# W707H.net
KiCad netlist of a schematic drawn in EAGLE
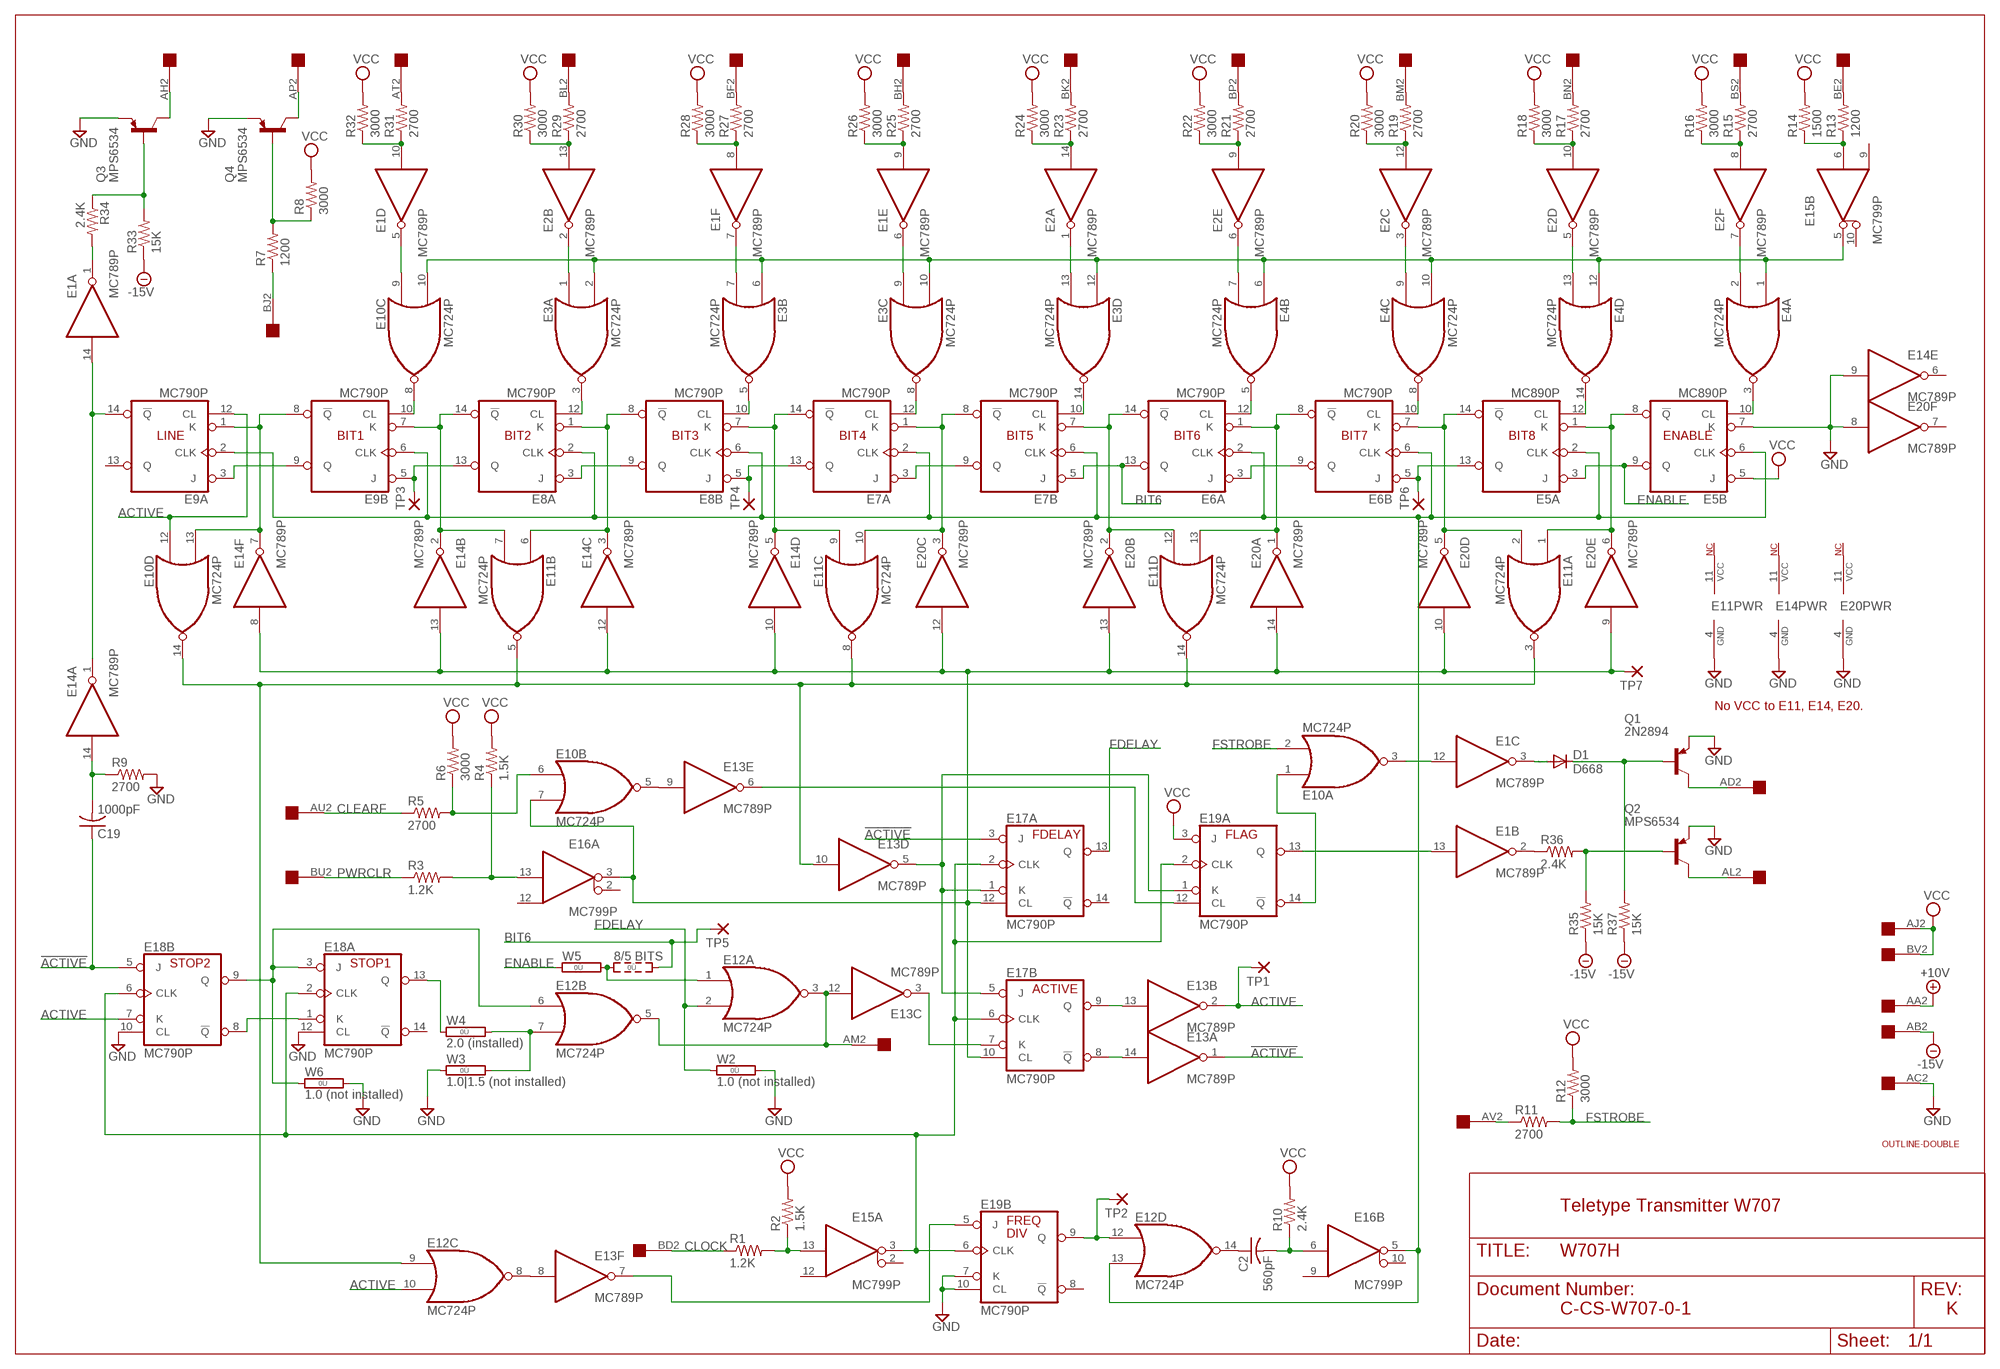
[diagram p0: schematic, sheet 1]

(export (version "E")
  (design (tool "Eeschema 10.0.6"))
  (components
    (comp (ref "C2")
      (value "560pF")
      (footprint "eagle-import:C050-025X075")
      (libsource (lib "eagle-import") (part "C-US050-025X075"))
    )
    (comp (ref "C19")
      (value "1000pF")
      (footprint "eagle-import:C050-025X075")
      (libsource (lib "eagle-import") (part "C-US050-025X075"))
    )
    (comp (ref "D1")
      (value "D668")
      (footprint "eagle-import:DO35-10")
      (libsource (lib "eagle-import") (part "1N4148DO35-10"))
    )
    (comp (ref "E1")
      (value "MC789P")
      (footprint "eagle-import:DIL14")
      (libsource (lib "eagle-import") (part "MC889P"))
    )
    (comp (ref "E2")
      (value "MC789P")
      (footprint "eagle-import:DIL14")
      (libsource (lib "eagle-import") (part "MC889P"))
    )
    (comp (ref "E3")
      (value "MC724P")
      (footprint "eagle-import:DIL14")
      (libsource (lib "eagle-import") (part "MC824P"))
    )
    (comp (ref "E4")
      (value "MC724P")
      (footprint "eagle-import:DIL14")
      (libsource (lib "eagle-import") (part "MC824P"))
    )
    (comp (ref "E5")
      (value "MC890P")
      (footprint "eagle-import:DIL14")
      (libsource (lib "eagle-import") (part "MC890P"))
    )
    (comp (ref "E6")
      (value "MC790P")
      (footprint "eagle-import:DIL14")
      (libsource (lib "eagle-import") (part "MC890P"))
    )
    (comp (ref "E7")
      (value "MC790P")
      (footprint "eagle-import:DIL14")
      (libsource (lib "eagle-import") (part "MC890P"))
    )
    (comp (ref "E8")
      (value "MC790P")
      (footprint "eagle-import:DIL14")
      (libsource (lib "eagle-import") (part "MC890P"))
    )
    (comp (ref "E9")
      (value "MC790P")
      (footprint "eagle-import:DIL14")
      (libsource (lib "eagle-import") (part "MC890P"))
    )
    (comp (ref "E10")
      (value "MC724P")
      (footprint "eagle-import:DIL14")
      (libsource (lib "eagle-import") (part "MC824P"))
    )
    (comp (ref "E11")
      (value "MC724P")
      (footprint "eagle-import:DIL14")
      (libsource (lib "eagle-import") (part "MC824P"))
    )
    (comp (ref "E12")
      (value "MC724P")
      (footprint "eagle-import:DIL14")
      (libsource (lib "eagle-import") (part "MC824P"))
    )
    (comp (ref "E13")
      (value "MC789P")
      (footprint "eagle-import:DIL14")
      (libsource (lib "eagle-import") (part "MC889P"))
    )
    (comp (ref "E14")
      (value "MC789P")
      (footprint "eagle-import:DIL14")
      (libsource (lib "eagle-import") (part "MC889P"))
    )
    (comp (ref "E15")
      (value "MC799P")
      (footprint "eagle-import:DIL14")
      (libsource (lib "eagle-import") (part "MC899P"))
    )
    (comp (ref "E16")
      (value "MC799P")
      (footprint "eagle-import:DIL14")
      (libsource (lib "eagle-import") (part "MC899P"))
    )
    (comp (ref "E17")
      (value "MC790P")
      (footprint "eagle-import:DIL14")
      (libsource (lib "eagle-import") (part "MC890P"))
    )
    (comp (ref "E18")
      (value "MC790P")
      (footprint "eagle-import:DIL14")
      (libsource (lib "eagle-import") (part "MC890P"))
    )
    (comp (ref "E19")
      (value "MC790P")
      (footprint "eagle-import:DIL14")
      (libsource (lib "eagle-import") (part "MC890P"))
    )
    (comp (ref "E20")
      (value "MC789P")
      (footprint "eagle-import:DIL14")
      (libsource (lib "eagle-import") (part "MC889P"))
    )
    (comp (ref "Q1")
      (value "2N2894")
      (footprint "eagle-import:TO39")
      (libsource (lib "eagle-import") (part "2N2904"))
    )
    (comp (ref "Q2")
      (value "MPS6534")
      (footprint "eagle-import:TO39")
      (libsource (lib "eagle-import") (part "2N2904"))
    )
    (comp (ref "Q3")
      (value "MPS6534")
      (footprint "eagle-import:TO39")
      (libsource (lib "eagle-import") (part "2N2904"))
    )
    (comp (ref "Q4")
      (value "MPS6534")
      (footprint "eagle-import:TO39")
      (libsource (lib "eagle-import") (part "2N2904"))
    )
    (comp (ref "R1")
      (value "1.2K")
      (footprint "eagle-import:0207_10")
      (libsource (lib "eagle-import") (part "R-US_0207/10"))
    )
    (comp (ref "R2")
      (value "1.5K")
      (footprint "eagle-import:0207_10")
      (libsource (lib "eagle-import") (part "R-US_0207/10"))
    )
    (comp (ref "R3")
      (value "1.2K")
      (footprint "eagle-import:0207_10")
      (libsource (lib "eagle-import") (part "R-US_0207/10"))
    )
    (comp (ref "R4")
      (value "1.5K")
      (footprint "eagle-import:0207_10")
      (libsource (lib "eagle-import") (part "R-US_0207/10"))
    )
    (comp (ref "R5")
      (value "2700")
      (footprint "eagle-import:0207_10")
      (libsource (lib "eagle-import") (part "R-US_0207/10"))
    )
    (comp (ref "R6")
      (value "3000")
      (footprint "eagle-import:0207_10")
      (libsource (lib "eagle-import") (part "R-US_0207/10"))
    )
    (comp (ref "R7")
      (value "1200")
      (footprint "eagle-import:0207_10")
      (libsource (lib "eagle-import") (part "R-US_0207/10"))
    )
    (comp (ref "R8")
      (value "3000")
      (footprint "eagle-import:0207_10")
      (libsource (lib "eagle-import") (part "R-US_0207/10"))
    )
    (comp (ref "R9")
      (value "2700")
      (footprint "eagle-import:0207_10")
      (libsource (lib "eagle-import") (part "R-US_0207/10"))
    )
    (comp (ref "R10")
      (value "2.4K")
      (footprint "eagle-import:0207_10")
      (libsource (lib "eagle-import") (part "R-US_0207/10"))
    )
    (comp (ref "R11")
      (value "2700")
      (footprint "eagle-import:0207_10")
      (libsource (lib "eagle-import") (part "R-US_0207/10"))
    )
    (comp (ref "R12")
      (value "3000")
      (footprint "eagle-import:0207_10")
      (libsource (lib "eagle-import") (part "R-US_0207/10"))
    )
    (comp (ref "R13")
      (value "1200")
      (footprint "eagle-import:0207_10")
      (libsource (lib "eagle-import") (part "R-US_0207/10"))
    )
    (comp (ref "R14")
      (value "1500")
      (footprint "eagle-import:0207_10")
      (libsource (lib "eagle-import") (part "R-US_0207/10"))
    )
    (comp (ref "R15")
      (value "2700")
      (footprint "eagle-import:0207_10")
      (libsource (lib "eagle-import") (part "R-US_0207/10"))
    )
    (comp (ref "R16")
      (value "3000")
      (footprint "eagle-import:0207_10")
      (libsource (lib "eagle-import") (part "R-US_0207/10"))
    )
    (comp (ref "R17")
      (value "2700")
      (footprint "eagle-import:0207_10")
      (libsource (lib "eagle-import") (part "R-US_0207/10"))
    )
    (comp (ref "R18")
      (value "3000")
      (footprint "eagle-import:0207_10")
      (libsource (lib "eagle-import") (part "R-US_0207/10"))
    )
    (comp (ref "R19")
      (value "2700")
      (footprint "eagle-import:0207_10")
      (libsource (lib "eagle-import") (part "R-US_0207/10"))
    )
    (comp (ref "R20")
      (value "3000")
      (footprint "eagle-import:0207_10")
      (libsource (lib "eagle-import") (part "R-US_0207/10"))
    )
    (comp (ref "R21")
      (value "2700")
      (footprint "eagle-import:0207_10")
      (libsource (lib "eagle-import") (part "R-US_0207/10"))
    )
    (comp (ref "R22")
      (value "3000")
      (footprint "eagle-import:0207_10")
      (libsource (lib "eagle-import") (part "R-US_0207/10"))
    )
    (comp (ref "R23")
      (value "2700")
      (footprint "eagle-import:0207_10")
      (libsource (lib "eagle-import") (part "R-US_0207/10"))
    )
    (comp (ref "R24")
      (value "3000")
      (footprint "eagle-import:0207_10")
      (libsource (lib "eagle-import") (part "R-US_0207/10"))
    )
    (comp (ref "R25")
      (value "2700")
      (footprint "eagle-import:0207_10")
      (libsource (lib "eagle-import") (part "R-US_0207/10"))
    )
    (comp (ref "R26")
      (value "3000")
      (footprint "eagle-import:0207_10")
      (libsource (lib "eagle-import") (part "R-US_0207/10"))
    )
    (comp (ref "R27")
      (value "2700")
      (footprint "eagle-import:0207_10")
      (libsource (lib "eagle-import") (part "R-US_0207/10"))
    )
    (comp (ref "R28")
      (value "3000")
      (footprint "eagle-import:0207_10")
      (libsource (lib "eagle-import") (part "R-US_0207/10"))
    )
    (comp (ref "R29")
      (value "2700")
      (footprint "eagle-import:0207_10")
      (libsource (lib "eagle-import") (part "R-US_0207/10"))
    )
    (comp (ref "R30")
      (value "3000")
      (footprint "eagle-import:0207_10")
      (libsource (lib "eagle-import") (part "R-US_0207/10"))
    )
    (comp (ref "R31")
      (value "2700")
      (footprint "eagle-import:0207_10")
      (libsource (lib "eagle-import") (part "R-US_0207/10"))
    )
    (comp (ref "R32")
      (value "3000")
      (footprint "eagle-import:0207_10")
      (libsource (lib "eagle-import") (part "R-US_0207/10"))
    )
    (comp (ref "R33")
      (value "15K")
      (footprint "eagle-import:0207_10")
      (libsource (lib "eagle-import") (part "R-US_0207/10"))
    )
    (comp (ref "R34")
      (value "2.4K")
      (footprint "eagle-import:0207_10")
      (libsource (lib "eagle-import") (part "R-US_0207/10"))
    )
    (comp (ref "R35")
      (value "15K")
      (footprint "eagle-import:0207_10")
      (libsource (lib "eagle-import") (part "R-US_0207/10"))
    )
    (comp (ref "R36")
      (value "2.4K")
      (footprint "eagle-import:0207_10")
      (libsource (lib "eagle-import") (part "R-US_0207/10"))
    )
    (comp (ref "R37")
      (value "15K")
      (footprint "eagle-import:0207_10")
      (libsource (lib "eagle-import") (part "R-US_0207/10"))
    )
    (comp (ref "TP1")
      (value "3,17/1,3")
      (footprint "eagle-import:3,17_1,3")
      (libsource (lib "eagle-import") (part "3,17/1,3"))
    )
    (comp (ref "TP2")
      (value "3,17/1,3")
      (footprint "eagle-import:3,17_1,3")
      (libsource (lib "eagle-import") (part "3,17/1,3"))
    )
    (comp (ref "TP3")
      (value "3,17/1,3")
      (footprint "eagle-import:3,17_1,3")
      (libsource (lib "eagle-import") (part "3,17/1,3"))
    )
    (comp (ref "TP4")
      (value "3,17/1,3")
      (footprint "eagle-import:3,17_1,3")
      (libsource (lib "eagle-import") (part "3,17/1,3"))
    )
    (comp (ref "TP5")
      (value "3,17/1,3")
      (footprint "eagle-import:3,17_1,3")
      (libsource (lib "eagle-import") (part "3,17/1,3"))
    )
    (comp (ref "TP6")
      (value "3,17/1,3")
      (footprint "eagle-import:3,17_1,3")
      (libsource (lib "eagle-import") (part "3,17/1,3"))
    )
    (comp (ref "TP7")
      (value "3,17/1,3")
      (footprint "eagle-import:3,17_1,3")
      (libsource (lib "eagle-import") (part "3,17/1,3"))
    )
    (comp (ref "U$1")
      (value "OUTLINE-DOUBLE")
      (footprint "eagle-import:DOUBLE")
      (libsource (lib "eagle-import") (part "OUTLINE-DOUBLE"))
    )
    (comp (ref "U$2")
      (value "DOUBLE")
      (footprint "eagle-import:EDGE-CON4")
      (libsource (lib "eagle-import") (part "DOUBLE"))
    )
    (comp (ref "W2")
      (value "1.0 (not installed)")
      (footprint "eagle-import:0R_10")
      (libsource (lib "eagle-import") (part "0R"))
    )
    (comp (ref "W3")
      (value "1.0|1.5 (not installed)")
      (footprint "eagle-import:0R_10")
      (libsource (lib "eagle-import") (part "0R"))
    )
    (comp (ref "W4")
      (value "2.0 (installed)")
      (footprint "eagle-import:0R_10")
      (libsource (lib "eagle-import") (part "0R"))
    )
    (comp (ref "W5")
      (value "8/5 BITS")
      (footprint "eagle-import:0R2_10")
      (libsource (lib "eagle-import") (part "0R2"))
    )
    (comp (ref "W6")
      (value "1.0 (not installed)")
      (footprint "eagle-import:0R_10")
      (libsource (lib "eagle-import") (part "0R"))
    )
  )
  (nets
    (net (code "1") (name "+10V") (class "Default")
      (node (ref "U$2") (pin "AA2") (pinfunction "1_AA2") (pintype "bidirectional"))
    )
    (net (code "2") (name "-15V") (class "Default")
      (node (ref "R33") (pin "1") (pinfunction "1_1") (pintype "passive"))
      (node (ref "R35") (pin "1") (pinfunction "1_1") (pintype "passive"))
      (node (ref "R37") (pin "1") (pinfunction "1_1") (pintype "passive"))
      (node (ref "U$2") (pin "AB2") (pinfunction "1_AB2") (pintype "bidirectional"))
    )
    (net (code "3") (name "/ACTIVE") (class "Default")
      (node (ref "E10") (pin "12") (pinfunction "I0_12") (pintype "input"))
      (node (ref "E12") (pin "10") (pinfunction "I1_10") (pintype "input"))
      (node (ref "E13") (pin "2") (pinfunction "O_2") (pintype "output"))
      (node (ref "E18") (pin "7") (pinfunction "K_7") (pintype "input"))
      (node (ref "E9") (pin "12") (pinfunction "CL_12") (pintype "input"))
      (node (ref "TP1") (pin "1") (pinfunction "P_1") (pintype "passive"))
    )
    (net (code "4") (name "/BIT6") (class "Default")
      (node (ref "E6") (pin "13") (pinfunction "Q_13") (pintype "output"))
      (node (ref "E7") (pin "5") (pinfunction "J_5") (pintype "input"))
      (node (ref "TP5") (pin "1") (pinfunction "P_1") (pintype "passive"))
      (node (ref "W5") (pin "3") (pinfunction "3_3") (pintype "passive"))
    )
    (net (code "5") (name "/CLEARF") (class "Default")
      (node (ref "R5") (pin "1") (pinfunction "1_1") (pintype "passive"))
      (node (ref "U$2") (pin "AU2") (pinfunction "1_AU2") (pintype "bidirectional"))
    )
    (net (code "6") (name "/CLOCK") (class "Default")
      (node (ref "R1") (pin "1") (pinfunction "1_1") (pintype "passive"))
      (node (ref "U$2") (pin "BD2") (pinfunction "1_BD2") (pintype "bidirectional"))
    )
    (net (code "7") (name "/ENABLE") (class "Default")
      (node (ref "E5") (pin "3") (pinfunction "J_3") (pintype "input"))
      (node (ref "E5") (pin "9") (pinfunction "Q_9") (pintype "output"))
      (node (ref "W5") (pin "1") (pinfunction "1_1") (pintype "passive"))
    )
    (net (code "8") (name "/FDELAY") (class "Default")
      (node (ref "E12") (pin "2") (pinfunction "I1_2") (pintype "input"))
      (node (ref "E17") (pin "13") (pinfunction "Q_13") (pintype "output"))
      (node (ref "W2") (pin "1") (pinfunction "1_1") (pintype "passive"))
    )
    (net (code "9") (name "/FSTROBE") (class "Default")
      (node (ref "E10") (pin "2") (pinfunction "I1_2") (pintype "input"))
      (node (ref "R11") (pin "2") (pinfunction "2_2") (pintype "passive"))
      (node (ref "R12") (pin "1") (pinfunction "1_1") (pintype "passive"))
    )
    (net (code "10") (name "/PWRCLR") (class "Default")
      (node (ref "R3") (pin "1") (pinfunction "1_1") (pintype "passive"))
      (node (ref "U$2") (pin "BU2") (pinfunction "1_BU2") (pintype "bidirectional"))
    )
    (net (code "11") (name "/~{ACTIVE}") (class "Default")
      (node (ref "C19") (pin "1") (pinfunction "1_1") (pintype "passive"))
      (node (ref "E13") (pin "1") (pinfunction "O_1") (pintype "output"))
      (node (ref "E17") (pin "3") (pinfunction "J_3") (pintype "input"))
      (node (ref "E18") (pin "5") (pinfunction "J_5") (pintype "input"))
    )
    (net (code "12") (name "GND") (class "Default")
      (node (ref "E11") (pin "4") (pinfunction "GND_4") (pintype "power_in"))
      (node (ref "E14") (pin "4") (pinfunction "GND_4") (pintype "power_in"))
      (node (ref "E14") (pin "9") (pinfunction "I_9") (pintype "input"))
      (node (ref "E18") (pin "10") (pinfunction "CL_10") (pintype "input"))
      (node (ref "E18") (pin "12") (pinfunction "CL_12") (pintype "input"))
      (node (ref "E19") (pin "10") (pinfunction "CL_10") (pintype "input"))
      (node (ref "E19") (pin "7") (pinfunction "K_7") (pintype "input"))
      (node (ref "E20") (pin "4") (pinfunction "GND_4") (pintype "power_in"))
      (node (ref "E20") (pin "8") (pinfunction "I_8") (pintype "input"))
      (node (ref "E5") (pin "7") (pinfunction "K_7") (pintype "input"))
      (node (ref "Q1") (pin "1") (pinfunction "E_1") (pintype "passive"))
      (node (ref "Q2") (pin "1") (pinfunction "E_1") (pintype "passive"))
      (node (ref "Q3") (pin "1") (pinfunction "E_1") (pintype "passive"))
      (node (ref "Q4") (pin "1") (pinfunction "E_1") (pintype "passive"))
      (node (ref "R9") (pin "2") (pinfunction "2_2") (pintype "passive"))
      (node (ref "U$2") (pin "AC2") (pinfunction "1_AC2") (pintype "bidirectional"))
      (node (ref "W2") (pin "2") (pinfunction "2_2") (pintype "passive"))
      (node (ref "W3") (pin "1") (pinfunction "1_1") (pintype "passive"))
      (node (ref "W6") (pin "2") (pinfunction "2_2") (pintype "passive"))
    )
    (net (code "13") (name "NC") (class "Default")
      (node (ref "E11") (pin "11") (pinfunction "VCC_11") (pintype "power_in"))
      (node (ref "E14") (pin "11") (pinfunction "VCC_11") (pintype "power_in"))
      (node (ref "E20") (pin "11") (pinfunction "VCC_11") (pintype "power_in"))
    )
    (net (code "14") (name "Net-(E1A-O)") (class "Default")
      (node (ref "E1") (pin "1") (pinfunction "O_1") (pintype "output"))
      (node (ref "R34") (pin "2") (pinfunction "2_2") (pintype "passive"))
    )
    (net (code "15") (name "Net-(E1B-O)") (class "Default")
      (node (ref "E1") (pin "2") (pinfunction "O_2") (pintype "output"))
      (node (ref "R36") (pin "1") (pinfunction "1_1") (pintype "passive"))
    )
    (net (code "16") (name "Net-(E1C-O)") (class "Default")
      (node (ref "D1") (pin "A") (pinfunction "A_A") (pintype "passive"))
      (node (ref "E1") (pin "3") (pinfunction "O_3") (pintype "output"))
    )
    (net (code "17") (name "Net-(E1D-I)") (class "Default")
      (node (ref "E1") (pin "10") (pinfunction "I_10") (pintype "input"))
      (node (ref "R31") (pin "1") (pinfunction "1_1") (pintype "passive"))
      (node (ref "R32") (pin "1") (pinfunction "1_1") (pintype "passive"))
    )
    (net (code "18") (name "Net-(E1E-I)") (class "Default")
      (node (ref "E1") (pin "9") (pinfunction "I_9") (pintype "input"))
      (node (ref "R25") (pin "1") (pinfunction "1_1") (pintype "passive"))
      (node (ref "R26") (pin "1") (pinfunction "1_1") (pintype "passive"))
    )
    (net (code "19") (name "Net-(E1E-O)") (class "Default")
      (node (ref "E1") (pin "6") (pinfunction "O_6") (pintype "output"))
      (node (ref "E3") (pin "9") (pinfunction "I0_9") (pintype "input"))
    )
    (net (code "20") (name "Net-(E1F-I)") (class "Default")
      (node (ref "E1") (pin "8") (pinfunction "I_8") (pintype "input"))
      (node (ref "R27") (pin "1") (pinfunction "1_1") (pintype "passive"))
      (node (ref "R28") (pin "1") (pinfunction "1_1") (pintype "passive"))
    )
    (net (code "21") (name "Net-(E1F-O)") (class "Default")
      (node (ref "E1") (pin "7") (pinfunction "O_7") (pintype "output"))
      (node (ref "E3") (pin "7") (pinfunction "I1_7") (pintype "input"))
    )
    (net (code "22") (name "Net-(E2A-I)") (class "Default")
      (node (ref "E2") (pin "14") (pinfunction "I_14") (pintype "input"))
      (node (ref "R23") (pin "1") (pinfunction "1_1") (pintype "passive"))
      (node (ref "R24") (pin "1") (pinfunction "1_1") (pintype "passive"))
    )
    (net (code "23") (name "Net-(E2A-O)") (class "Default")
      (node (ref "E2") (pin "1") (pinfunction "O_1") (pintype "output"))
      (node (ref "E3") (pin "13") (pinfunction "I1_13") (pintype "input"))
    )
    (net (code "24") (name "Net-(E2B-I)") (class "Default")
      (node (ref "E2") (pin "13") (pinfunction "I_13") (pintype "input"))
      (node (ref "R29") (pin "1") (pinfunction "1_1") (pintype "passive"))
      (node (ref "R30") (pin "1") (pinfunction "1_1") (pintype "passive"))
    )
    (net (code "25") (name "Net-(E2B-O)") (class "Default")
      (node (ref "E2") (pin "2") (pinfunction "O_2") (pintype "output"))
      (node (ref "E3") (pin "1") (pinfunction "I0_1") (pintype "input"))
    )
    (net (code "26") (name "Net-(E2C-I)") (class "Default")
      (node (ref "E2") (pin "12") (pinfunction "I_12") (pintype "input"))
      (node (ref "R19") (pin "1") (pinfunction "1_1") (pintype "passive"))
      (node (ref "R20") (pin "1") (pinfunction "1_1") (pintype "passive"))
    )
    (net (code "27") (name "Net-(E2C-O)") (class "Default")
      (node (ref "E2") (pin "3") (pinfunction "O_3") (pintype "output"))
      (node (ref "E4") (pin "9") (pinfunction "I0_9") (pintype "input"))
    )
    (net (code "28") (name "Net-(E2D-I)") (class "Default")
      (node (ref "E2") (pin "10") (pinfunction "I_10") (pintype "input"))
      (node (ref "R17") (pin "1") (pinfunction "1_1") (pintype "passive"))
      (node (ref "R18") (pin "1") (pinfunction "1_1") (pintype "passive"))
    )
    (net (code "29") (name "Net-(E2D-O)") (class "Default")
      (node (ref "E2") (pin "5") (pinfunction "O_5") (pintype "output"))
      (node (ref "E4") (pin "13") (pinfunction "I1_13") (pintype "input"))
    )
    (net (code "30") (name "Net-(E2E-I)") (class "Default")
      (node (ref "E2") (pin "9") (pinfunction "I_9") (pintype "input"))
      (node (ref "R21") (pin "1") (pinfunction "1_1") (pintype "passive"))
      (node (ref "R22") (pin "1") (pinfunction "1_1") (pintype "passive"))
    )
    (net (code "31") (name "Net-(E2E-O)") (class "Default")
      (node (ref "E2") (pin "6") (pinfunction "O_6") (pintype "output"))
      (node (ref "E4") (pin "7") (pinfunction "I1_7") (pintype "input"))
    )
    (net (code "32") (name "Net-(E2F-I)") (class "Default")
      (node (ref "E2") (pin "8") (pinfunction "I_8") (pintype "input"))
      (node (ref "R15") (pin "1") (pinfunction "1_1") (pintype "passive"))
      (node (ref "R16") (pin "1") (pinfunction "1_1") (pintype "passive"))
    )
    (net (code "33") (name "Net-(E2F-O)") (class "Default")
      (node (ref "E2") (pin "7") (pinfunction "O_7") (pintype "output"))
      (node (ref "E4") (pin "2") (pinfunction "I1_2") (pintype "input"))
    )
    (net (code "34") (name "Net-(E3A-O)") (class "Default")
      (node (ref "E3") (pin "3") (pinfunction "O_3") (pintype "output"))
      (node (ref "E8") (pin "12") (pinfunction "CL_12") (pintype "input"))
    )
    (net (code "35") (name "Net-(E3B-O)") (class "Default")
      (node (ref "E3") (pin "5") (pinfunction "O_5") (pintype "output"))
      (node (ref "E8") (pin "10") (pinfunction "CL_10") (pintype "input"))
    )
    (net (code "36") (name "Net-(E3C-O)") (class "Default")
      (node (ref "E3") (pin "8") (pinfunction "O_8") (pintype "output"))
      (node (ref "E7") (pin "12") (pinfunction "CL_12") (pintype "input"))
    )
    (net (code "37") (name "Net-(E3D-O)") (class "Default")
      (node (ref "E3") (pin "14") (pinfunction "O_14") (pintype "output"))
      (node (ref "E7") (pin "10") (pinfunction "CL_10") (pintype "input"))
    )
    (net (code "38") (name "Net-(E4A-O)") (class "Default")
      (node (ref "E4") (pin "3") (pinfunction "O_3") (pintype "output"))
      (node (ref "E5") (pin "10") (pinfunction "CL_10") (pintype "input"))
    )
    (net (code "39") (name "Net-(E4B-O)") (class "Default")
      (node (ref "E4") (pin "5") (pinfunction "O_5") (pintype "output"))
      (node (ref "E6") (pin "12") (pinfunction "CL_12") (pintype "input"))
    )
    (net (code "40") (name "Net-(E4C-O)") (class "Default")
      (node (ref "E4") (pin "8") (pinfunction "O_8") (pintype "output"))
      (node (ref "E6") (pin "10") (pinfunction "CL_10") (pintype "input"))
    )
    (net (code "41") (name "Net-(E4D-O)") (class "Default")
      (node (ref "E4") (pin "14") (pinfunction "O_14") (pintype "output"))
      (node (ref "E5") (pin "12") (pinfunction "CL_12") (pintype "input"))
    )
    (net (code "42") (name "Net-(E5A-Q)") (class "Default")
      (node (ref "E5") (pin "13") (pinfunction "Q_13") (pintype "output"))
      (node (ref "E6") (pin "5") (pinfunction "J_5") (pintype "input"))
      (node (ref "TP6") (pin "1") (pinfunction "P_1") (pintype "passive"))
    )
    (net (code "43") (name "Net-(E6A-J)") (class "Default")
      (node (ref "E6") (pin "3") (pinfunction "J_3") (pintype "input"))
      (node (ref "E6") (pin "9") (pinfunction "Q_9") (pintype "output"))
    )
    (net (code "44") (name "Net-(E7A-J)") (class "Default")
      (node (ref "E7") (pin "3") (pinfunction "J_3") (pintype "input"))
      (node (ref "E7") (pin "9") (pinfunction "Q_9") (pintype "output"))
    )
    (net (code "45") (name "Net-(E7A-Q)") (class "Default")
      (node (ref "E7") (pin "13") (pinfunction "Q_13") (pintype "output"))
      (node (ref "E8") (pin "5") (pinfunction "J_5") (pintype "input"))
      (node (ref "TP4") (pin "1") (pinfunction "P_1") (pintype "passive"))
    )
    (net (code "46") (name "Net-(E8A-J)") (class "Default")
      (node (ref "E8") (pin "3") (pinfunction "J_3") (pintype "input"))
      (node (ref "E8") (pin "9") (pinfunction "Q_9") (pintype "output"))
    )
    (net (code "47") (name "Net-(E8A-Q)") (class "Default")
      (node (ref "E8") (pin "13") (pinfunction "Q_13") (pintype "output"))
      (node (ref "E9") (pin "5") (pinfunction "J_5") (pintype "input"))
      (node (ref "TP3") (pin "1") (pinfunction "P_1") (pintype "passive"))
    )
    (net (code "48") (name "Net-(E9A-J)") (class "Default")
      (node (ref "E9") (pin "3") (pinfunction "J_3") (pintype "input"))
      (node (ref "E9") (pin "9") (pinfunction "Q_9") (pintype "output"))
    )
    (net (code "49") (name "Net-(E10A-I0)") (class "Default")
      (node (ref "E10") (pin "1") (pinfunction "I0_1") (pintype "input"))
      (node (ref "E19") (pin "14") (pinfunction "~{Q}_14") (pintype "output"))
    )
    (net (code "50") (name "Net-(E10A-O)") (class "Default")
      (node (ref "E1") (pin "12") (pinfunction "I_12") (pintype "input"))
      (node (ref "E10") (pin "3") (pinfunction "O_3") (pintype "output"))
    )
    (net (code "51") (name "Net-(E10B-I0)") (class "Default")
      (node (ref "E10") (pin "6") (pinfunction "I0_6") (pintype "input"))
      (node (ref "R5") (pin "2") (pinfunction "2_2") (pintype "passive"))
      (node (ref "R6") (pin "1") (pinfunction "1_1") (pintype "passive"))
    )
    (net (code "52") (name "Net-(E10B-I1)") (class "Default")
      (node (ref "E10") (pin "7") (pinfunction "I1_7") (pintype "input"))
      (node (ref "E14") (pin "10") (pinfunction "I_10") (pintype "input"))
      (node (ref "E14") (pin "12") (pinfunction "I_12") (pintype "input"))
      (node (ref "E14") (pin "13") (pinfunction "I_13") (pintype "input"))
      (node (ref "E14") (pin "8") (pinfunction "I_8") (pintype "input"))
      (node (ref "E16") (pin "3") (pinfunction "O_3") (pintype "output"))
      (node (ref "E17") (pin "10") (pinfunction "CL_10") (pintype "input"))
      (node (ref "E17") (pin "12") (pinfunction "CL_12") (pintype "input"))
      (node (ref "E20") (pin "10") (pinfunction "I_10") (pintype "input"))
      (node (ref "E20") (pin "12") (pinfunction "I_12") (pintype "input"))
      (node (ref "E20") (pin "13") (pinfunction "I_13") (pintype "input"))
      (node (ref "E20") (pin "14") (pinfunction "I_14") (pintype "input"))
      (node (ref "E20") (pin "9") (pinfunction "I_9") (pintype "input"))
      (node (ref "TP7") (pin "1") (pinfunction "P_1") (pintype "passive"))
    )
    (net (code "53") (name "Net-(E10B-O)") (class "Default")
      (node (ref "E10") (pin "5") (pinfunction "O_5") (pintype "output"))
      (node (ref "E13") (pin "9") (pinfunction "I_9") (pintype "input"))
    )
    (net (code "54") (name "Net-(E10C-I0)") (class "Default")
      (node (ref "E1") (pin "5") (pinfunction "O_5") (pintype "output"))
      (node (ref "E10") (pin "9") (pinfunction "I0_9") (pintype "input"))
    )
    (net (code "55") (name "Net-(E10C-I1)") (class "Default")
      (node (ref "E10") (pin "10") (pinfunction "I1_10") (pintype "input"))
      (node (ref "E15") (pin "5") (pinfunction "O_5") (pintype "output"))
      (node (ref "E3") (pin "10") (pinfunction "I1_10") (pintype "input"))
      (node (ref "E3") (pin "12") (pinfunction "I0_12") (pintype "input"))
      (node (ref "E3") (pin "2") (pinfunction "I1_2") (pintype "input"))
      (node (ref "E3") (pin "6") (pinfunction "I0_6") (pintype "input"))
      (node (ref "E4") (pin "1") (pinfunction "I0_1") (pintype "input"))
      (node (ref "E4") (pin "10") (pinfunction "I1_10") (pintype "input"))
      (node (ref "E4") (pin "12") (pinfunction "I0_12") (pintype "input"))
      (node (ref "E4") (pin "6") (pinfunction "I0_6") (pintype "input"))
    )
    (net (code "56") (name "Net-(E10C-O)") (class "Default")
      (node (ref "E10") (pin "8") (pinfunction "O_8") (pintype "output"))
      (node (ref "E9") (pin "10") (pinfunction "CL_10") (pintype "input"))
    )
    (net (code "57") (name "Net-(E10D-I1)") (class "Default")
      (node (ref "E10") (pin "13") (pinfunction "I1_13") (pintype "input"))
      (node (ref "E14") (pin "7") (pinfunction "O_7") (pintype "output"))
      (node (ref "E9") (pin "1") (pinfunction "K_1") (pintype "input"))
      (node (ref "E9") (pin "8") (pinfunction "~{Q}_8") (pintype "output"))
    )
    (net (code "58") (name "Net-(E10D-O)") (class "Default")
      (node (ref "E10") (pin "14") (pinfunction "O_14") (pintype "output"))
      (node (ref "E11") (pin "14") (pinfunction "O_14") (pintype "output"))
      (node (ref "E11") (pin "3") (pinfunction "O_3") (pintype "output"))
      (node (ref "E11") (pin "5") (pinfunction "O_5") (pintype "output"))
      (node (ref "E11") (pin "8") (pinfunction "O_8") (pintype "output"))
      (node (ref "E12") (pin "9") (pinfunction "I0_9") (pintype "input"))
      (node (ref "E13") (pin "10") (pinfunction "I_10") (pintype "input"))
    )
    (net (code "59") (name "Net-(E11A-I0)") (class "Default")
      (node (ref "E11") (pin "1") (pinfunction "I0_1") (pintype "input"))
      (node (ref "E20") (pin "6") (pinfunction "O_6") (pintype "output"))
      (node (ref "E5") (pin "1") (pinfunction "K_1") (pintype "input"))
      (node (ref "E5") (pin "8") (pinfunction "~{Q}_8") (pintype "output"))
    )
    (net (code "60") (name "Net-(E11A-I1)") (class "Default")
      (node (ref "E11") (pin "2") (pinfunction "I1_2") (pintype "input"))
      (node (ref "E20") (pin "5") (pinfunction "O_5") (pintype "output"))
      (node (ref "E5") (pin "14") (pinfunction "~{Q}_14") (pintype "output"))
      (node (ref "E6") (pin "7") (pinfunction "K_7") (pintype "input"))
    )
    (net (code "61") (name "Net-(E11B-I0)") (class "Default")
      (node (ref "E11") (pin "6") (pinfunction "I0_6") (pintype "input"))
      (node (ref "E14") (pin "3") (pinfunction "O_3") (pintype "output"))
      (node (ref "E8") (pin "1") (pinfunction "K_1") (pintype "input"))
      (node (ref "E8") (pin "8") (pinfunction "~{Q}_8") (pintype "output"))
    )
    (net (code "62") (name "Net-(E11B-I1)") (class "Default")
      (node (ref "E11") (pin "7") (pinfunction "I1_7") (pintype "input"))
      (node (ref "E14") (pin "2") (pinfunction "O_2") (pintype "output"))
      (node (ref "E8") (pin "14") (pinfunction "~{Q}_14") (pintype "output"))
      (node (ref "E9") (pin "7") (pinfunction "K_7") (pintype "input"))
    )
    (net (code "63") (name "Net-(E11C-I0)") (class "Default")
      (node (ref "E11") (pin "9") (pinfunction "I0_9") (pintype "input"))
      (node (ref "E14") (pin "5") (pinfunction "O_5") (pintype "output"))
      (node (ref "E7") (pin "14") (pinfunction "~{Q}_14") (pintype "output"))
      (node (ref "E8") (pin "7") (pinfunction "K_7") (pintype "input"))
    )
    (net (code "64") (name "Net-(E11C-I1)") (class "Default")
      (node (ref "E11") (pin "10") (pinfunction "I1_10") (pintype "input"))
      (node (ref "E20") (pin "3") (pinfunction "O_3") (pintype "output"))
      (node (ref "E7") (pin "1") (pinfunction "K_1") (pintype "input"))
      (node (ref "E7") (pin "8") (pinfunction "~{Q}_8") (pintype "output"))
    )
    (net (code "65") (name "Net-(E11D-I0)") (class "Default")
      (node (ref "E11") (pin "12") (pinfunction "I0_12") (pintype "input"))
      (node (ref "E20") (pin "2") (pinfunction "O_2") (pintype "output"))
      (node (ref "E6") (pin "14") (pinfunction "~{Q}_14") (pintype "output"))
      (node (ref "E7") (pin "7") (pinfunction "K_7") (pintype "input"))
    )
    (net (code "66") (name "Net-(E11D-I1)") (class "Default")
      (node (ref "E11") (pin "13") (pinfunction "I1_13") (pintype "input"))
      (node (ref "E20") (pin "1") (pinfunction "O_1") (pintype "output"))
      (node (ref "E6") (pin "1") (pinfunction "K_1") (pintype "input"))
      (node (ref "E6") (pin "8") (pinfunction "~{Q}_8") (pintype "output"))
    )
    (net (code "67") (name "Net-(E12A-I0)") (class "Default")
      (node (ref "E12") (pin "1") (pinfunction "I0_1") (pintype "input"))
      (node (ref "W5") (pin "2") (pinfunction "2_2") (pintype "passive"))
    )
    (net (code "68") (name "Net-(E12A-O)") (class "Default")
      (node (ref "E12") (pin "3") (pinfunction "O_3") (pintype "output"))
      (node (ref "E12") (pin "5") (pinfunction "O_5") (pintype "output"))
      (node (ref "E13") (pin "12") (pinfunction "I_12") (pintype "input"))
      (node (ref "U$2") (pin "AM2") (pinfunction "1_AM2") (pintype "bidirectional"))
    )
    (net (code "69") (name "Net-(E12B-I0)") (class "Default")
      (node (ref "E12") (pin "6") (pinfunction "I0_6") (pintype "input"))
      (node (ref "E18") (pin "3") (pinfunction "J_3") (pintype "input"))
      (node (ref "E18") (pin "9") (pinfunction "Q_9") (pintype "output"))
      (node (ref "W6") (pin "1") (pinfunction "1_1") (pintype "passive"))
    )
    (net (code "70") (name "Net-(E12B-I1)") (class "Default")
      (node (ref "E12") (pin "7") (pinfunction "I1_7") (pintype "input"))
      (node (ref "W3") (pin "2") (pinfunction "2_2") (pintype "passive"))
      (node (ref "W4") (pin "2") (pinfunction "2_2") (pintype "passive"))
    )
    (net (code "71") (name "Net-(E12C-O)") (class "Default")
      (node (ref "E12") (pin "8") (pinfunction "O_8") (pintype "output"))
      (node (ref "E13") (pin "8") (pinfunction "I_8") (pintype "input"))
    )
    (net (code "72") (name "Net-(E12D-I0)") (class "Default")
      (node (ref "E12") (pin "12") (pinfunction "I0_12") (pintype "input"))
      (node (ref "E19") (pin "9") (pinfunction "Q_9") (pintype "output"))
      (node (ref "TP2") (pin "1") (pinfunction "P_1") (pintype "passive"))
    )
    (net (code "73") (name "Net-(E12D-I1)") (class "Default")
      (node (ref "E12") (pin "13") (pinfunction "I1_13") (pintype "input"))
      (node (ref "E16") (pin "5") (pinfunction "O_5") (pintype "output"))
      (node (ref "E5") (pin "2") (pinfunction "CLK_2") (pintype "input"))
      (node (ref "E5") (pin "6") (pinfunction "CLK_6") (pintype "input"))
      (node (ref "E6") (pin "2") (pinfunction "CLK_2") (pintype "input"))
      (node (ref "E6") (pin "6") (pinfunction "CLK_6") (pintype "input"))
      (node (ref "E7") (pin "2") (pinfunction "CLK_2") (pintype "input"))
      (node (ref "E7") (pin "6") (pinfunction "CLK_6") (pintype "input"))
      (node (ref "E8") (pin "2") (pinfunction "CLK_2") (pintype "input"))
      (node (ref "E8") (pin "6") (pinfunction "CLK_6") (pintype "input"))
      (node (ref "E9") (pin "2") (pinfunction "CLK_2") (pintype "input"))
      (node (ref "E9") (pin "6") (pinfunction "CLK_6") (pintype "input"))
    )
    (net (code "74") (name "Net-(E12D-O)") (class "Default")
      (node (ref "C2") (pin "1") (pinfunction "1_1") (pintype "passive"))
      (node (ref "E12") (pin "14") (pinfunction "O_14") (pintype "output"))
    )
    (net (code "75") (name "Net-(E13A-I)") (class "Default")
      (node (ref "E13") (pin "14") (pinfunction "I_14") (pintype "input"))
      (node (ref "E17") (pin "8") (pinfunction "~{Q}_8") (pintype "output"))
    )
    (net (code "76") (name "Net-(E13B-I)") (class "Default")
      (node (ref "E13") (pin "13") (pinfunction "I_13") (pintype "input"))
      (node (ref "E17") (pin "9") (pinfunction "Q_9") (pintype "output"))
    )
    (net (code "77") (name "Net-(E13C-O)") (class "Default")
      (node (ref "E13") (pin "3") (pinfunction "O_3") (pintype "output"))
      (node (ref "E17") (pin "7") (pinfunction "K_7") (pintype "input"))
    )
    (net (code "78") (name "Net-(E13D-O)") (class "Default")
      (node (ref "E13") (pin "5") (pinfunction "O_5") (pintype "output"))
      (node (ref "E17") (pin "1") (pinfunction "K_1") (pintype "input"))
      (node (ref "E17") (pin "5") (pinfunction "J_5") (pintype "input"))
      (node (ref "E19") (pin "1") (pinfunction "K_1") (pintype "input"))
    )
    (net (code "79") (name "Net-(E13E-O)") (class "Default")
      (node (ref "E13") (pin "6") (pinfunction "O_6") (pintype "output"))
      (node (ref "E19") (pin "12") (pinfunction "CL_12") (pintype "input"))
    )
    (net (code "80") (name "Net-(E13F-O)") (class "Default")
      (node (ref "E13") (pin "7") (pinfunction "O_7") (pintype "output"))
      (node (ref "E19") (pin "5") (pinfunction "J_5") (pintype "input"))
    )
    (net (code "81") (name "Net-(E14A-I)") (class "Default")
      (node (ref "C19") (pin "2") (pinfunction "2_2") (pintype "passive"))
      (node (ref "E14") (pin "14") (pinfunction "I_14") (pintype "input"))
      (node (ref "R9") (pin "1") (pinfunction "1_1") (pintype "passive"))
    )
    (net (code "82") (name "Net-(E14A-O)") (class "Default")
      (node (ref "E1") (pin "14") (pinfunction "I_14") (pintype "input"))
      (node (ref "E14") (pin "1") (pinfunction "O_1") (pintype "output"))
      (node (ref "E9") (pin "14") (pinfunction "~{Q}_14") (pintype "output"))
    )
    (net (code "83") (name "Net-(E15A-I)") (class "Default")
      (node (ref "E15") (pin "13") (pinfunction "I_13") (pintype "input"))
      (node (ref "R1") (pin "2") (pinfunction "2_2") (pintype "passive"))
      (node (ref "R2") (pin "1") (pinfunction "1_1") (pintype "passive"))
    )
    (net (code "84") (name "Net-(E15A-O)") (class "Default")
      (node (ref "E15") (pin "3") (pinfunction "O_3") (pintype "output"))
      (node (ref "E17") (pin "2") (pinfunction "CLK_2") (pintype "input"))
      (node (ref "E17") (pin "6") (pinfunction "CLK_6") (pintype "input"))
      (node (ref "E18") (pin "2") (pinfunction "CLK_2") (pintype "input"))
      (node (ref "E18") (pin "6") (pinfunction "CLK_6") (pintype "input"))
      (node (ref "E19") (pin "2") (pinfunction "CLK_2") (pintype "input"))
      (node (ref "E19") (pin "6") (pinfunction "CLK_6") (pintype "input"))
    )
    (net (code "85") (name "Net-(E15B-I)") (class "Default")
      (node (ref "E15") (pin "6") (pinfunction "I_6") (pintype "input"))
      (node (ref "R13") (pin "1") (pinfunction "1_1") (pintype "passive"))
      (node (ref "R14") (pin "1") (pinfunction "1_1") (pintype "passive"))
    )
    (net (code "86") (name "Net-(E16A-I)") (class "Default")
      (node (ref "E16") (pin "13") (pinfunction "I_13") (pintype "input"))
      (node (ref "R3") (pin "2") (pinfunction "2_2") (pintype "passive"))
      (node (ref "R4") (pin "1") (pinfunction "1_1") (pintype "passive"))
    )
    (net (code "87") (name "Net-(E16B-I)") (class "Default")
      (node (ref "C2") (pin "2") (pinfunction "2_2") (pintype "passive"))
      (node (ref "E16") (pin "6") (pinfunction "I_6") (pintype "input"))
      (node (ref "R10") (pin "1") (pinfunction "1_1") (pintype "passive"))
    )
    (net (code "88") (name "Net-(E18A-K)") (class "Default")
      (node (ref "E18") (pin "1") (pinfunction "K_1") (pintype "input"))
      (node (ref "E18") (pin "8") (pinfunction "~{Q}_8") (pintype "output"))
    )
    (net (code "89") (name "Net-(E18A-Q)") (class "Default")
      (node (ref "E18") (pin "13") (pinfunction "Q_13") (pintype "output"))
      (node (ref "W4") (pin "1") (pinfunction "1_1") (pintype "passive"))
    )
    (net (code "90") (name "Net-(E19A-Q)") (class "Default")
      (node (ref "E1") (pin "13") (pinfunction "I_13") (pintype "input"))
      (node (ref "E19") (pin "13") (pinfunction "Q_13") (pintype "output"))
    )
    (net (code "91") (name "Net-(Q1-B)") (class "Default")
      (node (ref "D1") (pin "C") (pinfunction "C_C") (pintype "passive"))
      (node (ref "Q1") (pin "2") (pinfunction "B_2") (pintype "passive"))
      (node (ref "R37") (pin "2") (pinfunction "2_2") (pintype "passive"))
    )
    (net (code "92") (name "Net-(Q1-C)") (class "Default")
      (node (ref "Q1") (pin "3") (pinfunction "C_3") (pintype "passive"))
      (node (ref "U$2") (pin "AD2") (pinfunction "1_AD2") (pintype "bidirectional"))
    )
    (net (code "93") (name "Net-(Q2-B)") (class "Default")
      (node (ref "Q2") (pin "2") (pinfunction "B_2") (pintype "passive"))
      (node (ref "R35") (pin "2") (pinfunction "2_2") (pintype "passive"))
      (node (ref "R36") (pin "2") (pinfunction "2_2") (pintype "passive"))
    )
    (net (code "94") (name "Net-(Q2-C)") (class "Default")
      (node (ref "Q2") (pin "3") (pinfunction "C_3") (pintype "passive"))
      (node (ref "U$2") (pin "AL2") (pinfunction "1_AL2") (pintype "bidirectional"))
    )
    (net (code "95") (name "Net-(Q3-B)") (class "Default")
      (node (ref "Q3") (pin "2") (pinfunction "B_2") (pintype "passive"))
      (node (ref "R33") (pin "2") (pinfunction "2_2") (pintype "passive"))
      (node (ref "R34") (pin "1") (pinfunction "1_1") (pintype "passive"))
    )
    (net (code "96") (name "Net-(Q3-C)") (class "Default")
      (node (ref "Q3") (pin "3") (pinfunction "C_3") (pintype "passive"))
      (node (ref "U$2") (pin "AH2") (pinfunction "1_AH2") (pintype "bidirectional"))
    )
    (net (code "97") (name "Net-(Q4-B)") (class "Default")
      (node (ref "Q4") (pin "2") (pinfunction "B_2") (pintype "passive"))
      (node (ref "R7") (pin "2") (pinfunction "2_2") (pintype "passive"))
      (node (ref "R8") (pin "1") (pinfunction "1_1") (pintype "passive"))
    )
    (net (code "98") (name "Net-(Q4-C)") (class "Default")
      (node (ref "Q4") (pin "3") (pinfunction "C_3") (pintype "passive"))
      (node (ref "U$2") (pin "AP2") (pinfunction "1_AP2") (pintype "bidirectional"))
    )
    (net (code "99") (name "Net-(U$2AF-1)") (class "Default")
      (node (ref "R31") (pin "2") (pinfunction "2_2") (pintype "passive"))
      (node (ref "U$2") (pin "AT2") (pinfunction "1_AT2") (pintype "bidirectional"))
    )
    (net (code "100") (name "Net-(U$2AJ-1)") (class "Default")
      (node (ref "R11") (pin "1") (pinfunction "1_1") (pintype "passive"))
      (node (ref "U$2") (pin "AV2") (pinfunction "1_AV2") (pintype "bidirectional"))
    )
    (net (code "101") (name "Net-(U$2AT-1)") (class "Default")
      (node (ref "R13") (pin "2") (pinfunction "2_2") (pintype "passive"))
      (node (ref "U$2") (pin "BE2") (pinfunction "1_BE2") (pintype "bidirectional"))
    )
    (net (code "102") (name "Net-(U$2AV-1)") (class "Default")
      (node (ref "R27") (pin "2") (pinfunction "2_2") (pintype "passive"))
      (node (ref "U$2") (pin "BF2") (pinfunction "1_BF2") (pintype "bidirectional"))
    )
    (net (code "103") (name "Net-(U$2AX-1)") (class "Default")
      (node (ref "R25") (pin "2") (pinfunction "2_2") (pintype "passive"))
      (node (ref "U$2") (pin "BH2") (pinfunction "1_BH2") (pintype "bidirectional"))
    )
    (net (code "104") (name "Net-(U$2AZ-1)") (class "Default")
      (node (ref "R7") (pin "1") (pinfunction "1_1") (pintype "passive"))
      (node (ref "U$2") (pin "BJ2") (pinfunction "1_BJ2") (pintype "bidirectional"))
    )
    (net (code "105") (name "Net-(U$2BB-1)") (class "Default")
      (node (ref "R23") (pin "2") (pinfunction "2_2") (pintype "passive"))
      (node (ref "U$2") (pin "BK2") (pinfunction "1_BK2") (pintype "bidirectional"))
    )
    (net (code "106") (name "Net-(U$2BD-1)") (class "Default")
      (node (ref "R29") (pin "2") (pinfunction "2_2") (pintype "passive"))
      (node (ref "U$2") (pin "BL2") (pinfunction "1_BL2") (pintype "bidirectional"))
    )
    (net (code "107") (name "Net-(U$2BF-1)") (class "Default")
      (node (ref "R19") (pin "2") (pinfunction "2_2") (pintype "passive"))
      (node (ref "U$2") (pin "BM2") (pinfunction "1_BM2") (pintype "bidirectional"))
    )
    (net (code "108") (name "Net-(U$2BH-1)") (class "Default")
      (node (ref "R17") (pin "2") (pinfunction "2_2") (pintype "passive"))
      (node (ref "U$2") (pin "BN2") (pinfunction "1_BN2") (pintype "bidirectional"))
    )
    (net (code "109") (name "Net-(U$2BJ-1)") (class "Default")
      (node (ref "R21") (pin "2") (pinfunction "2_2") (pintype "passive"))
      (node (ref "U$2") (pin "BP2") (pinfunction "1_BP2") (pintype "bidirectional"))
    )
    (net (code "110") (name "Net-(U$2BN-1)") (class "Default")
      (node (ref "R15") (pin "2") (pinfunction "2_2") (pintype "passive"))
      (node (ref "U$2") (pin "BS2") (pinfunction "1_BS2") (pintype "bidirectional"))
    )
    (net (code "111") (name "VCC") (class "Default")
      (node (ref "E19") (pin "3") (pinfunction "J_3") (pintype "input"))
      (node (ref "E5") (pin "5") (pinfunction "J_5") (pintype "input"))
      (node (ref "R10") (pin "2") (pinfunction "2_2") (pintype "passive"))
      (node (ref "R12") (pin "2") (pinfunction "2_2") (pintype "passive"))
      (node (ref "R14") (pin "2") (pinfunction "2_2") (pintype "passive"))
      (node (ref "R16") (pin "2") (pinfunction "2_2") (pintype "passive"))
      (node (ref "R18") (pin "2") (pinfunction "2_2") (pintype "passive"))
      (node (ref "R2") (pin "2") (pinfunction "2_2") (pintype "passive"))
      (node (ref "R20") (pin "2") (pinfunction "2_2") (pintype "passive"))
      (node (ref "R22") (pin "2") (pinfunction "2_2") (pintype "passive"))
      (node (ref "R24") (pin "2") (pinfunction "2_2") (pintype "passive"))
      (node (ref "R26") (pin "2") (pinfunction "2_2") (pintype "passive"))
      (node (ref "R28") (pin "2") (pinfunction "2_2") (pintype "passive"))
      (node (ref "R30") (pin "2") (pinfunction "2_2") (pintype "passive"))
      (node (ref "R32") (pin "2") (pinfunction "2_2") (pintype "passive"))
      (node (ref "R4") (pin "2") (pinfunction "2_2") (pintype "passive"))
      (node (ref "R6") (pin "2") (pinfunction "2_2") (pintype "passive"))
      (node (ref "R8") (pin "2") (pinfunction "2_2") (pintype "passive"))
      (node (ref "U$2") (pin "AJ2") (pinfunction "1_AJ2") (pintype "bidirectional"))
      (node (ref "U$2") (pin "BV2") (pinfunction "1_BV2") (pintype "bidirectional"))
    )
    (net (code "112") (name "unconnected-(E9A-Q-Pad13)") (class "Default")
      (node (ref "E9") (pin "13") (pinfunction "Q_13") (pintype "output"))
    )
    (net (code "113") (name "unconnected-(E14E-O-Pad6)") (class "Default")
      (node (ref "E14") (pin "6") (pinfunction "O_6") (pintype "output"))
    )
    (net (code "114") (name "unconnected-(E15A-E-Pad2)") (class "Default")
      (node (ref "E15") (pin "2") (pinfunction "E_2") (pintype "output"))
    )
    (net (code "115") (name "unconnected-(E15A-R-Pad12)") (class "Default")
      (node (ref "E15") (pin "12") (pinfunction "R_12") (pintype "passive"))
    )
    (net (code "116") (name "unconnected-(E15B-E-Pad10)") (class "Default")
      (node (ref "E15") (pin "10") (pinfunction "E_10") (pintype "output"))
    )
    (net (code "117") (name "unconnected-(E15B-R-Pad9)") (class "Default")
      (node (ref "E15") (pin "9") (pinfunction "R_9") (pintype "passive"))
    )
    (net (code "118") (name "unconnected-(E16A-E-Pad2)") (class "Default")
      (node (ref "E16") (pin "2") (pinfunction "E_2") (pintype "output"))
    )
    (net (code "119") (name "unconnected-(E16A-R-Pad12)") (class "Default")
      (node (ref "E16") (pin "12") (pinfunction "R_12") (pintype "passive"))
    )
    (net (code "120") (name "unconnected-(E16B-E-Pad10)") (class "Default")
      (node (ref "E16") (pin "10") (pinfunction "E_10") (pintype "output"))
    )
    (net (code "121") (name "unconnected-(E16B-R-Pad9)") (class "Default")
      (node (ref "E16") (pin "9") (pinfunction "R_9") (pintype "passive"))
    )
    (net (code "122") (name "unconnected-(E17A-~{Q}-Pad14)") (class "Default")
      (node (ref "E17") (pin "14") (pinfunction "~{Q}_14") (pintype "output"))
    )
    (net (code "123") (name "unconnected-(E18A-~{Q}-Pad14)") (class "Default")
      (node (ref "E18") (pin "14") (pinfunction "~{Q}_14") (pintype "output"))
    )
    (net (code "124") (name "unconnected-(E19B-~{Q}-Pad8)") (class "Default")
      (node (ref "E19") (pin "8") (pinfunction "~{Q}_8") (pintype "output"))
    )
    (net (code "125") (name "unconnected-(E20F-O-Pad7)") (class "Default")
      (node (ref "E20") (pin "7") (pinfunction "O_7") (pintype "output"))
    )
  )
)
